# Arduino__Connectors.net
KiCad netlist of a schematic drawn in Altium Designer
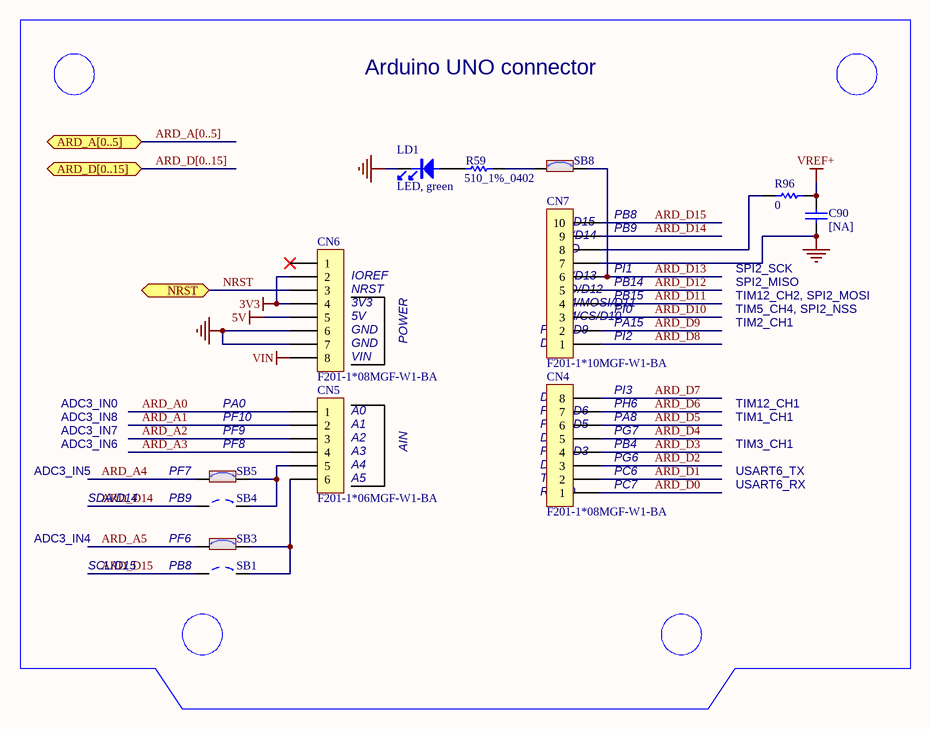
[diagram p0: Arduino_ Connectors.SchDoc]

(export (version "E")
  (design (tool "Eeschema 10.0.6"))
  (components
    (comp (ref "C90")
      (value "[NA]")
      (footprint "0402C")
      (description "Capacitor,NA,0402")
      (libsource (lib "MCD_TOOLS") (part "Cap_NA_0402"))
    )
    (comp (ref "CN4")
      (value "F201-1*08MGF-W1-BA")
      (footprint "F201-1*08MGF-W1-BA")
      (description "Header, 8-Pins, Single row, female SMD")
      (libsource (lib "") (part "F201-1*08MGF-W1-BA_1"))
    )
    (comp (ref "CN5")
      (value "F201-1*06MGF-W1-BA")
      (footprint "F201-1*06MGF-W1-BA")
      (description "Header, 6-Pins, Single row, female SMD")
      (libsource (lib "MCD_TOOLS") (part "F201-1*06MGF-W1-BA"))
    )
    (comp (ref "CN6")
      (value "F201-1*08MGF-W1-BA")
      (footprint "F201-1*08MGF-W1-BA")
      (description "Header, 8-Pins, Single row, female SMD")
      (libsource (lib "MCD_TOOLS") (part "F201-1*08MGF-W1-BA"))
    )
    (comp (ref "CN7")
      (value "F201-1*10MGF-W1-BA")
      (footprint "F201-1*10MGF-W1-BA")
      (description "Header, 8-Pins, Single row, female SMD")
      (libsource (lib "MCD_TOOLS") (part "F201-1*10MGF-W1-BA"))
    )
    (comp (ref "LD1")
      (value "LED, green")
      (footprint "0603D")
      (description "LED,green,0603,19-213SYGC/S530-E2/TR8,everlight")
      (libsource (lib "MCD_TOOLS") (part "LED_green"))
    )
    (comp (ref "R59")
      (value "510_1%_0402")
      (footprint "0402R")
      (description "Resistor,510,0402,1%,YAGEO")
      (libsource (lib "MCD_TOOLS") (part "Res_510_1%_0402"))
    )
    (comp (ref "R96")
      (value "0")
      (footprint "0402R")
      (description "Resistor,0,0402,5%,YAGEO")
      (libsource (lib "MCD_TOOLS") (part "Res_0_5%_0402"))
    )
    (comp (ref "SB1")
      (value "Solder Bridge OFF")
      (footprint "JP2_SMD")
      (libsource (lib "MCD_TOOLS") (part "SB_OFF"))
    )
    (comp (ref "SB3")
      (value "Solder Bridge ON")
      (footprint "JP2_SMD")
      (libsource (lib "MCD_TOOLS") (part "SB_ON"))
    )
    (comp (ref "SB4")
      (value "Solder Bridge OFF")
      (footprint "JP2_SMD")
      (libsource (lib "MCD_TOOLS") (part "SB_OFF"))
    )
    (comp (ref "SB5")
      (value "Solder Bridge ON")
      (footprint "JP2_SMD")
      (libsource (lib "MCD_TOOLS") (part "SB_ON"))
    )
    (comp (ref "SB8")
      (value "Solder Bridge ON")
      (footprint "JP2_SMD")
      (libsource (lib "MCD_TOOLS") (part "SB_ON"))
    )
  )
  (nets
    (net (code "1") (name "/ARD_A0") (class "Default")
      (node (ref "CN5") (pin "1") (pinfunction "1_1") (pintype "passive"))
    )
    (net (code "2") (name "/ARD_A1") (class "Default")
      (node (ref "CN5") (pin "2") (pinfunction "2_2") (pintype "passive"))
    )
    (net (code "3") (name "/ARD_A2") (class "Default")
      (node (ref "CN5") (pin "3") (pinfunction "3_3") (pintype "passive"))
    )
    (net (code "4") (name "/ARD_A3") (class "Default")
      (node (ref "CN5") (pin "4") (pinfunction "4_4") (pintype "passive"))
    )
    (net (code "5") (name "/ARD_A4") (class "Default")
      (node (ref "SB5") (pin "1") (pinfunction "1_1") (pintype "passive"))
    )
    (net (code "6") (name "/ARD_A5") (class "Default")
      (node (ref "SB3") (pin "1") (pinfunction "1_1") (pintype "passive"))
    )
    (net (code "8") (name "/ARD_D0") (class "Default")
      (node (ref "CN4") (pin "1") (pinfunction "1_1") (pintype "passive"))
    )
    (net (code "9") (name "/ARD_D1") (class "Default")
      (node (ref "CN4") (pin "2") (pinfunction "2_2") (pintype "passive"))
    )
    (net (code "10") (name "/ARD_D2") (class "Default")
      (node (ref "CN4") (pin "3") (pinfunction "3_3") (pintype "passive"))
    )
    (net (code "11") (name "/ARD_D3") (class "Default")
      (node (ref "CN4") (pin "4") (pinfunction "4_4") (pintype "passive"))
    )
    (net (code "12") (name "/ARD_D4") (class "Default")
      (node (ref "CN4") (pin "5") (pinfunction "5_5") (pintype "passive"))
    )
    (net (code "13") (name "/ARD_D5") (class "Default")
      (node (ref "CN4") (pin "6") (pinfunction "6_6") (pintype "passive"))
    )
    (net (code "14") (name "/ARD_D6") (class "Default")
      (node (ref "CN4") (pin "7") (pinfunction "7_7") (pintype "passive"))
    )
    (net (code "15") (name "/ARD_D7") (class "Default")
      (node (ref "CN4") (pin "8") (pinfunction "8_8") (pintype "passive"))
    )
    (net (code "16") (name "/ARD_D8") (class "Default")
      (node (ref "CN7") (pin "1") (pinfunction "1_1") (pintype "passive"))
    )
    (net (code "17") (name "/ARD_D9") (class "Default")
      (node (ref "CN7") (pin "2") (pinfunction "2_2") (pintype "passive"))
    )
    (net (code "18") (name "/ARD_D10") (class "Default")
      (node (ref "CN7") (pin "3") (pinfunction "3_3") (pintype "passive"))
    )
    (net (code "19") (name "/ARD_D11") (class "Default")
      (node (ref "CN7") (pin "4") (pinfunction "4_4") (pintype "passive"))
    )
    (net (code "20") (name "/ARD_D12") (class "Default")
      (node (ref "CN7") (pin "5") (pinfunction "5_5") (pintype "passive"))
    )
    (net (code "21") (name "/ARD_D13") (class "Default")
      (node (ref "CN7") (pin "6") (pinfunction "6_6") (pintype "passive"))
      (node (ref "SB8") (pin "2") (pinfunction "2_2") (pintype "passive"))
    )
    (net (code "22") (name "/ARD_D14") (class "Default")
      (node (ref "CN7") (pin "9") (pinfunction "9_9") (pintype "passive"))
      (node (ref "SB4") (pin "1") (pinfunction "1_1") (pintype "passive"))
    )
    (net (code "23") (name "/ARD_D15") (class "Default")
      (node (ref "CN7") (pin "10") (pinfunction "10_10") (pintype "passive"))
      (node (ref "SB1") (pin "1") (pinfunction "1_1") (pintype "passive"))
    )
    (net (code "25") (name "/NRST") (class "Default")
      (node (ref "CN6") (pin "3") (pinfunction "3_3") (pintype "passive"))
    )
    (net (code "26") (name "3V3") (class "Default")
      (node (ref "CN6") (pin "2") (pinfunction "2_2") (pintype "passive"))
      (node (ref "CN6") (pin "4") (pinfunction "4_4") (pintype "passive"))
    )
    (net (code "27") (name "5V") (class "Default")
      (node (ref "CN6") (pin "5") (pinfunction "5_5") (pintype "passive"))
    )
    (net (code "28") (name "GND") (class "Default")
      (node (ref "C90") (pin "1") (pinfunction "1_1") (pintype "passive"))
      (node (ref "CN6") (pin "6") (pinfunction "6_6") (pintype "passive"))
      (node (ref "CN6") (pin "7") (pinfunction "7_7") (pintype "passive"))
      (node (ref "CN7") (pin "7") (pinfunction "7_7") (pintype "passive"))
      (node (ref "LD1") (pin "2") (pintype "passive"))
    )
    (net (code "29") (name "Net-(CN5-Pad5)") (class "Default")
      (node (ref "CN5") (pin "5") (pinfunction "5_5") (pintype "passive"))
      (node (ref "SB4") (pin "2") (pinfunction "2_2") (pintype "passive"))
      (node (ref "SB5") (pin "2") (pinfunction "2_2") (pintype "passive"))
    )
    (net (code "30") (name "Net-(CN5-Pad6)") (class "Default")
      (node (ref "CN5") (pin "6") (pinfunction "6_6") (pintype "passive"))
      (node (ref "SB1") (pin "2") (pinfunction "2_2") (pintype "passive"))
      (node (ref "SB3") (pin "2") (pinfunction "2_2") (pintype "passive"))
    )
    (net (code "31") (name "Net-(CN7-Pad8)") (class "Default")
      (node (ref "CN7") (pin "8") (pinfunction "8_8") (pintype "passive"))
      (node (ref "R96") (pin "1") (pinfunction "1_1") (pintype "passive"))
    )
    (net (code "32") (name "Net-(LD1-Pad1)") (class "Default")
      (node (ref "LD1") (pin "1") (pintype "passive"))
      (node (ref "R59") (pin "1") (pinfunction "1_1") (pintype "passive"))
    )
    (net (code "33") (name "Net-(R59-Pad2)") (class "Default")
      (node (ref "R59") (pin "2") (pinfunction "2_2") (pintype "passive"))
      (node (ref "SB8") (pin "1") (pinfunction "1_1") (pintype "passive"))
    )
    (net (code "34") (name "VIN") (class "Default")
      (node (ref "CN6") (pin "8") (pinfunction "8_8") (pintype "passive"))
    )
    (net (code "35") (name "VREF+") (class "Default")
      (node (ref "C90") (pin "2") (pinfunction "2_2") (pintype "passive"))
      (node (ref "R96") (pin "2") (pinfunction "2_2") (pintype "passive"))
    )
    (net (code "36") (name "unconnected-(CN6-Pad1)") (class "Default")
      (node (ref "CN6") (pin "1") (pinfunction "1_1") (pintype "passive+no_connect"))
    )
  )
)
